# LB_BIT_oX_1IN_1OUT-XXL-v03_1_1x.net
KiCad netlist of a schematic drawn in EAGLE
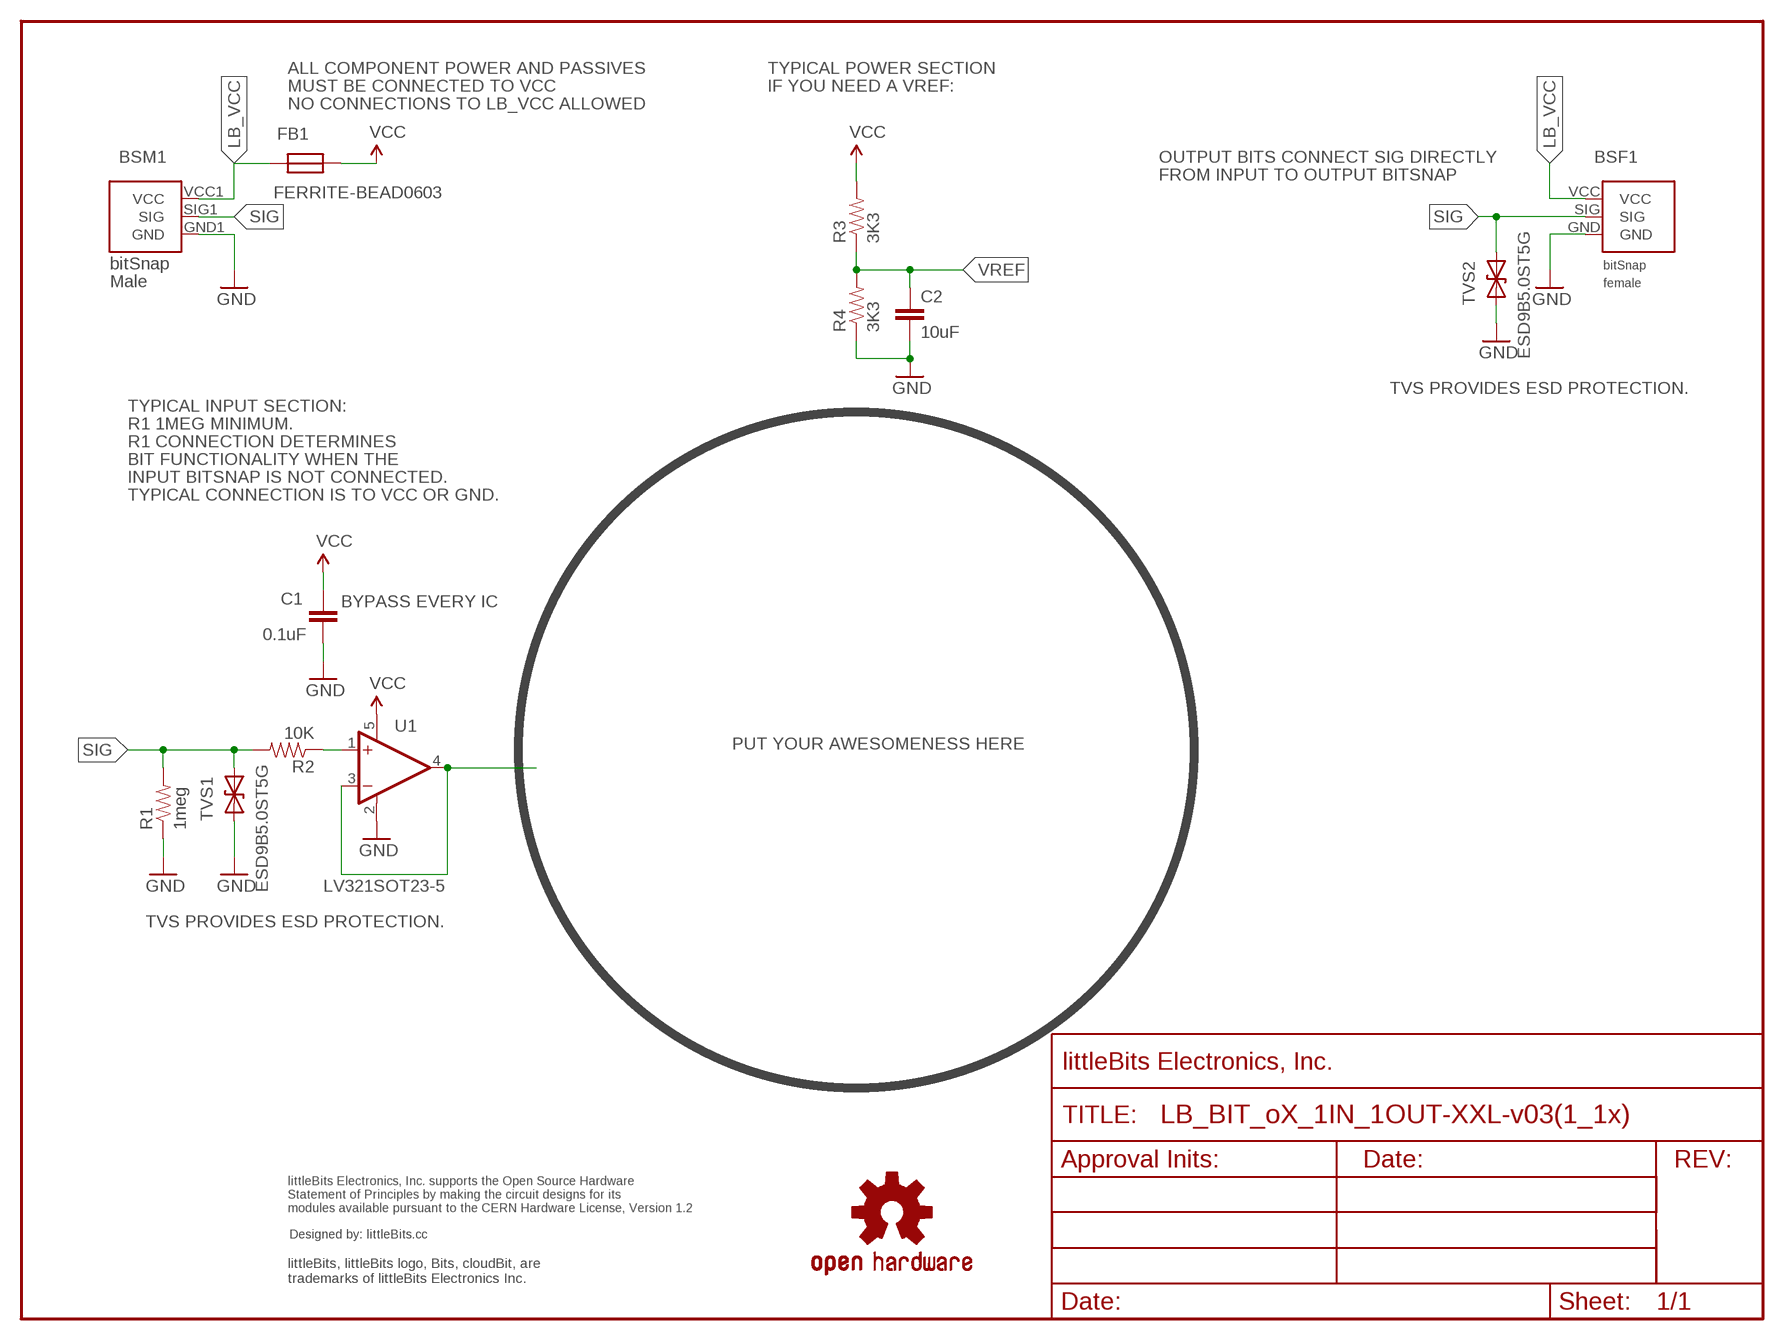
[diagram p0: schematic, sheet 1]

(export (version "E")
  (design (tool "Eeschema 10.0.6"))
  (components
    (comp (ref "BSF1")
      (value "BITSNAP_V03_FEMALE")
      (footprint "eagle-import:BITSNAP_V03_FEMALE")
      (libsource (lib "eagle-import") (part "BITSNAP_V03_FEMALE"))
    )
    (comp (ref "BSM1")
      (value "BITSNAP_V03_MALE")
      (footprint "eagle-import:BITSNAP_V03_MALE")
      (libsource (lib "eagle-import") (part "BITSNAP_V03_MALE"))
    )
    (comp (ref "C1")
      (value "0.1uF")
      (footprint "eagle-import:CAP-0603")
      (libsource (lib "eagle-import") (part "CAPCAP-0603"))
    )
    (comp (ref "C2")
      (value "10uF")
      (footprint "eagle-import:CAP-0603")
      (libsource (lib "eagle-import") (part "CAPCAP-0603"))
    )
    (comp (ref "FB1")
      (value "FERRITE-BEAD0603")
      (footprint "eagle-import:R0603")
      (libsource (lib "eagle-import") (part "FERRITE-BEAD0603"))
    )
    (comp (ref "R1")
      (value "1meg")
      (footprint "eagle-import:RES-0603")
      (libsource (lib "eagle-import") (part "RESISTOR0603"))
    )
    (comp (ref "R2")
      (value "10K")
      (footprint "eagle-import:RES-0603")
      (libsource (lib "eagle-import") (part "RESISTOR0603"))
    )
    (comp (ref "R3")
      (value "3K3")
      (footprint "eagle-import:RES-0603")
      (libsource (lib "eagle-import") (part "RESISTOR0603"))
    )
    (comp (ref "R4")
      (value "3K3")
      (footprint "eagle-import:RES-0603")
      (libsource (lib "eagle-import") (part "RESISTOR0603"))
    )
    (comp (ref "TVS1")
      (value "ESD9B5.0ST5G")
      (footprint "eagle-import:SOD-923")
      (libsource (lib "eagle-import") (part "DIODE-TVSSOD-923"))
    )
    (comp (ref "TVS2")
      (value "ESD9B5.0ST5G")
      (footprint "eagle-import:SOD-923")
      (libsource (lib "eagle-import") (part "DIODE-TVSSOD-923"))
    )
    (comp (ref "U$1")
      (value "OSHW-LOGOL")
      (footprint "eagle-import:OSHW-LOGO-L")
      (libsource (lib "eagle-import") (part "OSHW-LOGOL"))
    )
    (comp (ref "U$2")
      (value "OSHWCREDIT")
      (footprint "eagle-import:OSHWCREDIT")
      (libsource (lib "eagle-import") (part "OSHWCREDIT"))
    )
    (comp (ref "U$3")
      (value "FRAME-LETTER")
      (footprint "eagle-import:FABDWG01-OHW")
      (libsource (lib "eagle-import") (part "FRAME-LETTER"))
    )
    (comp (ref "U1")
      (value "LV321SOT23-5")
      (footprint "eagle-import:SOT23-5")
      (libsource (lib "eagle-import") (part "LV321SOT23-5"))
    )
  )
  (nets
    (net (code "1") (name "GND") (class "Default")
      (node (ref "BSF1") (pin "GND") (pinfunction "GND_GND") (pintype "bidirectional"))
      (node (ref "BSM1") (pin "GND1") (pinfunction "GND_GND1") (pintype "bidirectional"))
      (node (ref "C1") (pin "2") (pinfunction "2_2") (pintype "passive"))
      (node (ref "C2") (pin "2") (pinfunction "2_2") (pintype "passive"))
      (node (ref "R1") (pin "1") (pinfunction "1_1") (pintype "passive"))
      (node (ref "R4") (pin "1") (pinfunction "1_1") (pintype "passive"))
      (node (ref "TVS1") (pin "1") (pinfunction "A_1") (pintype "passive"))
      (node (ref "TVS2") (pin "1") (pinfunction "A_1") (pintype "passive"))
      (node (ref "U1") (pin "2") (pinfunction "V-_2") (pintype "power_in"))
    )
    (net (code "2") (name "LB_VCC") (class "Default")
      (node (ref "BSF1") (pin "VCC") (pinfunction "VCC_VCC") (pintype "bidirectional"))
      (node (ref "BSM1") (pin "VCC1") (pinfunction "VCC_VCC1") (pintype "bidirectional"))
      (node (ref "FB1") (pin "2") (pinfunction "P$2_2") (pintype "bidirectional"))
    )
    (net (code "3") (name "Net-(U1-+IN)") (class "Default")
      (node (ref "R2") (pin "1") (pinfunction "1_1") (pintype "passive"))
      (node (ref "U1") (pin "1") (pinfunction "+IN_1") (pintype "input"))
    )
    (net (code "4") (name "Net-(U1--IN)") (class "Default")
      (node (ref "U1") (pin "3") (pinfunction "-IN_3") (pintype "input"))
      (node (ref "U1") (pin "4") (pinfunction "OUT_4") (pintype "output"))
    )
    (net (code "5") (name "SIG") (class "Default")
      (node (ref "BSF1") (pin "SIG") (pinfunction "SIG_SIG") (pintype "bidirectional"))
      (node (ref "BSM1") (pin "SIG1") (pinfunction "SIG_SIG1") (pintype "bidirectional"))
      (node (ref "R1") (pin "2") (pinfunction "2_2") (pintype "passive"))
      (node (ref "R2") (pin "2") (pinfunction "2_2") (pintype "passive"))
      (node (ref "TVS1") (pin "2") (pinfunction "C_2") (pintype "passive"))
      (node (ref "TVS2") (pin "2") (pinfunction "C_2") (pintype "passive"))
    )
    (net (code "6") (name "VCC") (class "Default")
      (node (ref "C1") (pin "1") (pinfunction "1_1") (pintype "passive"))
      (node (ref "FB1") (pin "1") (pinfunction "P$1_1") (pintype "bidirectional"))
      (node (ref "R3") (pin "2") (pinfunction "2_2") (pintype "passive"))
      (node (ref "U1") (pin "5") (pinfunction "V+_5") (pintype "power_in"))
    )
    (net (code "7") (name "VREF") (class "Default")
      (node (ref "C2") (pin "1") (pinfunction "1_1") (pintype "passive"))
      (node (ref "R3") (pin "1") (pinfunction "1_1") (pintype "passive"))
      (node (ref "R4") (pin "2") (pinfunction "2_2") (pintype "passive"))
    )
  )
)
